# Headphone-Amplifier-ClassAB-13x6.net
KiCad netlist of a schematic drawn in EAGLE
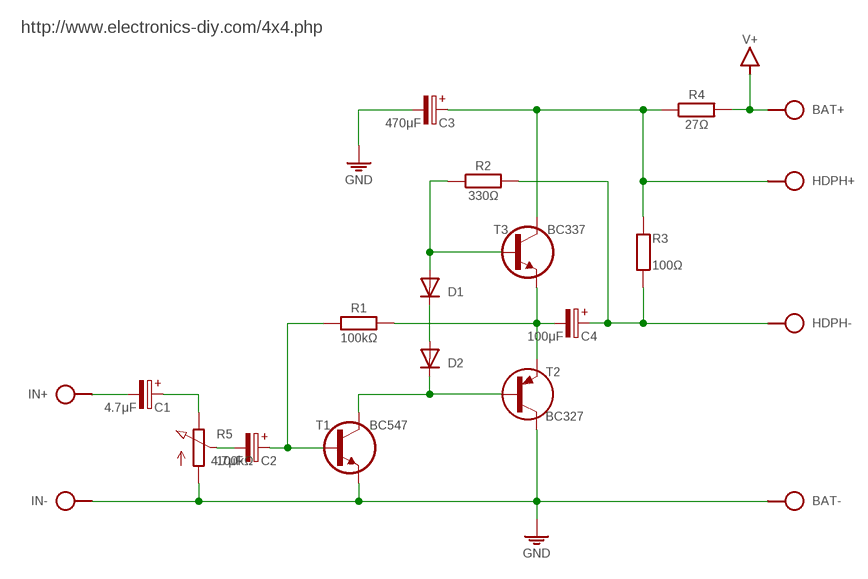
[diagram p0: schematic, sheet 1]

(export (version "E")
  (design (tool "Eeschema 10.0.6"))
  (components
    (comp (ref "BAT")
      (value "SPAD+-+-")
      (footprint "eagle-import:SPAD+-")
      (libsource (lib "eagle-import") (part "SPAD+-+-"))
    )
    (comp (ref "C1")
      (value "4.7μF")
      (footprint "eagle-import:E2,5-4")
      (libsource (lib "eagle-import") (part "CPOL-HE2,5-4"))
    )
    (comp (ref "C2")
      (value "4.7μF")
      (footprint "eagle-import:E2,5-4")
      (libsource (lib "eagle-import") (part "CPOL-HE2,5-4"))
    )
    (comp (ref "C3")
      (value "470μF")
      (footprint "eagle-import:E5-5")
      (libsource (lib "eagle-import") (part "CPOL-HE5-5"))
    )
    (comp (ref "C4")
      (value "100μF")
      (footprint "eagle-import:E2,5-4")
      (libsource (lib "eagle-import") (part "CPOL-HE2,5-4"))
    )
    (comp (ref "D1")
      (value "1N414834-5V")
      (footprint "eagle-import:DO34-5V")
      (libsource (lib "eagle-import") (part "1N414834-5V"))
    )
    (comp (ref "D2")
      (value "1N414834-5V")
      (footprint "eagle-import:DO34-5V")
      (libsource (lib "eagle-import") (part "1N414834-5V"))
    )
    (comp (ref "HDPH")
      (value "SPAD+--+")
      (footprint "eagle-import:SPAD-+")
      (libsource (lib "eagle-import") (part "SPAD+--+"))
    )
    (comp (ref "IN")
      (value "SPAD+--+")
      (footprint "eagle-import:SPAD-+")
      (libsource (lib "eagle-import") (part "SPAD+--+"))
    )
    (comp (ref "R1")
      (value "100kΩ")
      (footprint "eagle-import:0202_7")
      (libsource (lib "eagle-import") (part "R-H0202/7"))
    )
    (comp (ref "R2")
      (value "330Ω")
      (footprint "eagle-import:0202_7")
      (libsource (lib "eagle-import") (part "R-H0202/7"))
    )
    (comp (ref "R3")
      (value "100Ω")
      (footprint "eagle-import:0202_7")
      (libsource (lib "eagle-import") (part "R0202/7"))
    )
    (comp (ref "R4")
      (value "27Ω")
      (footprint "eagle-import:0204V")
      (libsource (lib "eagle-import") (part "R-H-V-X"))
    )
    (comp (ref "R5")
      (value "100kΩ")
      (footprint "eagle-import:CONN-3P")
      (libsource (lib "eagle-import") (part "POT-3P"))
    )
    (comp (ref "T1")
      (value "BC547")
      (footprint "eagle-import:TO92-CBE")
      (libsource (lib "eagle-import") (part "BC547CBE"))
    )
    (comp (ref "T2")
      (value "BC327")
      (footprint "eagle-import:TO92")
      (libsource (lib "eagle-import") (part "BC327"))
    )
    (comp (ref "T3")
      (value "BC337")
      (footprint "eagle-import:TO92-CBE")
      (libsource (lib "eagle-import") (part "BC337CBE"))
    )
  )
  (nets
    (net (code "1") (name "GND") (class "Default")
      (node (ref "BAT") (pin "1") (pinfunction "P$1_1") (pintype "passive"))
      (node (ref "C3") (pin "-") (pinfunction "-_-") (pintype "passive"))
      (node (ref "IN") (pin "1") (pinfunction "P$1_1") (pintype "passive"))
      (node (ref "R5") (pin "1") (pinfunction "A_1") (pintype "passive"))
      (node (ref "T1") (pin "E") (pinfunction "E_E") (pintype "passive"))
      (node (ref "T2") (pin "1") (pinfunction "C_1") (pintype "passive"))
    )
    (net (code "2") (name "Net-(C2-Pad+)") (class "Default")
      (node (ref "C2") (pin "+") (pinfunction "+_+") (pintype "passive"))
      (node (ref "R1") (pin "1") (pinfunction "1_1") (pintype "passive"))
      (node (ref "T1") (pin "B") (pinfunction "B_B") (pintype "passive"))
    )
    (net (code "3") (name "Net-(D1-PadA)") (class "Default")
      (node (ref "D1") (pin "A") (pinfunction "A_A") (pintype "passive"))
      (node (ref "R2") (pin "1") (pinfunction "1_1") (pintype "passive"))
      (node (ref "T3") (pin "B") (pinfunction "B_B") (pintype "passive"))
    )
    (net (code "4") (name "Net-(D1-PadC)") (class "Default")
      (node (ref "D1") (pin "C") (pinfunction "C_C") (pintype "passive"))
      (node (ref "D2") (pin "A") (pinfunction "A_A") (pintype "passive"))
    )
    (net (code "5") (name "Net-(HDPHA-P$1)") (class "Default")
      (node (ref "C3") (pin "+") (pinfunction "+_+") (pintype "passive"))
      (node (ref "HDPH") (pin "2") (pinfunction "P$1_2") (pintype "passive"))
      (node (ref "R3") (pin "2") (pinfunction "1_2") (pintype "passive"))
      (node (ref "R4") (pin "2") (pinfunction "1_2") (pintype "passive"))
      (node (ref "T3") (pin "C") (pinfunction "C_C") (pintype "passive"))
    )
    (net (code "6") (name "Net-(HDPHB-P$1)") (class "Default")
      (node (ref "C4") (pin "+") (pinfunction "+_+") (pintype "passive"))
      (node (ref "HDPH") (pin "1") (pinfunction "P$1_1") (pintype "passive"))
      (node (ref "R2") (pin "2") (pinfunction "2_2") (pintype "passive"))
      (node (ref "R3") (pin "1") (pinfunction "2_1") (pintype "passive"))
    )
    (net (code "7") (name "Net-(INA-P$1)") (class "Default")
      (node (ref "C1") (pin "-") (pinfunction "-_-") (pintype "passive"))
      (node (ref "IN") (pin "2") (pinfunction "P$1_2") (pintype "passive"))
    )
    (net (code "8") (name "Net-(R5-E)") (class "Default")
      (node (ref "C1") (pin "+") (pinfunction "+_+") (pintype "passive"))
      (node (ref "R5") (pin "3") (pinfunction "E_3") (pintype "passive"))
    )
    (net (code "9") (name "Net-(R5-S)") (class "Default")
      (node (ref "C2") (pin "-") (pinfunction "-_-") (pintype "passive"))
      (node (ref "R5") (pin "2") (pinfunction "S_2") (pintype "passive"))
    )
    (net (code "10") (name "Net-(T2-B)") (class "Default")
      (node (ref "D2") (pin "C") (pinfunction "C_C") (pintype "passive"))
      (node (ref "T1") (pin "C") (pinfunction "C_C") (pintype "passive"))
      (node (ref "T2") (pin "2") (pinfunction "B_2") (pintype "passive"))
    )
    (net (code "11") (name "Net-(T2-E)") (class "Default")
      (node (ref "C4") (pin "-") (pinfunction "-_-") (pintype "passive"))
      (node (ref "R1") (pin "2") (pinfunction "2_2") (pintype "passive"))
      (node (ref "T2") (pin "3") (pinfunction "E_3") (pintype "passive"))
      (node (ref "T3") (pin "E") (pinfunction "E_E") (pintype "passive"))
    )
    (net (code "12") (name "V+") (class "Default")
      (node (ref "BAT") (pin "2") (pinfunction "P$1_2") (pintype "passive"))
      (node (ref "R4") (pin "1") (pinfunction "2_1") (pintype "passive"))
    )
  )
)
